# 01-LcdText1602.net
KiCad netlist of a schematic drawn in Altium Designer
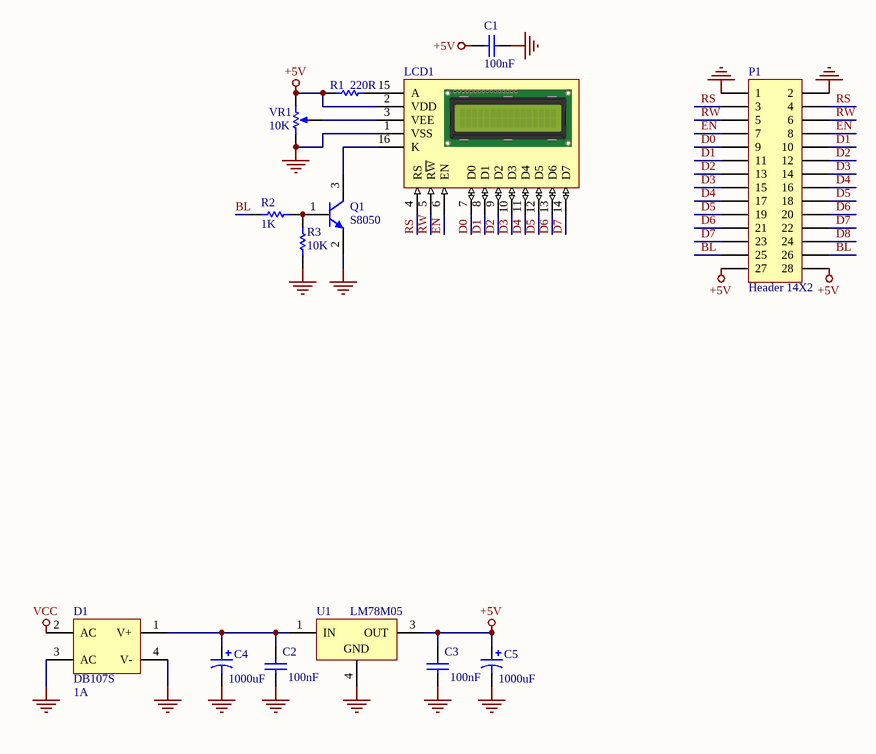
[diagram p0: 01-LcdText1602.SchDoc]

(export (version "E")
  (design (tool "Eeschema 10.0.6"))
  (components
    (comp (ref "C1")
      (value "100nF")
      (footprint "RAD-0.3")
      (description "Capacitor")
      (fields (field (name "Comment") "104") (field (name "PUBLISHER") "Altium Limited"))
      (libsource (lib "Miscellaneous Devices") (part "Cap"))
    )
    (comp (ref "C2")
      (value "100nF")
      (footprint "RAD-0.3")
      (description "Capacitor")
      (fields (field (name "Comment") "104") (field (name "PUBLISHER") "Altium Limited"))
      (libsource (lib "Miscellaneous Devices") (part "Cap"))
    )
    (comp (ref "C3")
      (value "100nF")
      (footprint "RAD-0.3")
      (description "Capacitor")
      (fields (field (name "Comment") "104") (field (name "PUBLISHER") "Altium Limited"))
      (libsource (lib "Miscellaneous Devices") (part "Cap"))
    )
    (comp (ref "C4")
      (value "1000uF")
      (footprint "RB7.6-15")
      (description "Polarized Capacitor (Radial)")
      (fields (field (name "Comment") "1000uF/16V") (field (name "PUBLISHER") "Altium Limited"))
      (libsource (lib "Miscellaneous Devices") (part "Cap Pol1"))
    )
    (comp (ref "C5")
      (value "1000uF")
      (footprint "RB7.6-15")
      (description "Polarized Capacitor (Radial)")
      (fields (field (name "Comment") "1000uF/16V") (field (name "PUBLISHER") "Altium Limited"))
      (libsource (lib "Miscellaneous Devices") (part "Cap Pol1"))
    )
    (comp (ref "D1")
      (value "DB107S")
      (footprint "D-46_6A")
      (description "Diode Bridge")
      (fields (field (name "ALTIUM_VALUE") "1A"))
      (libsource (lib "Miscellaneous Devices") (part "Bridge2"))
    )
    (comp (ref "LCD1")
      (value "16 x 2")
      (footprint "LCD16x2")
      (description "Liquid Crystal Display")
      (libsource (lib "Dlib") (part "LCD16X2"))
    )
    (comp (ref "P1")
      (value "Header 14X2")
      (footprint "HDR2X14")
      (description "Header, 14-Pin, Dual row")
      (fields (field (name "PUBLISHER") "Altium Limited"))
      (libsource (lib "Miscellaneous Connectors") (part "Header 14X2"))
    )
    (comp (ref "Q1")
      (value "S8050")
      (footprint "TO-226-AA")
      (description "NPN Bipolar Transistor")
      (libsource (lib "Miscellaneous Devices") (part "NPN"))
    )
    (comp (ref "R1")
      (value "220R")
      (footprint "AXIAL-0.3")
      (description "Resistor")
      (fields (field (name "PUBLISHER") "Altium Limited"))
      (libsource (lib "Miscellaneous Devices") (part "Res1"))
    )
    (comp (ref "R2")
      (value "1K")
      (footprint "AXIAL-0.3")
      (description "Resistor")
      (fields (field (name "PUBLISHER") "Altium Limited"))
      (libsource (lib "Miscellaneous Devices") (part "Res1"))
    )
    (comp (ref "R3")
      (value "10K")
      (footprint "AXIAL-0.3")
      (description "Resistor")
      (fields (field (name "PUBLISHER") "Altium Limited"))
      (libsource (lib "Miscellaneous Devices") (part "Res1"))
    )
    (comp (ref "U1")
      (value "LM78M05")
      (footprint "NDP0003B_M")
      (description "3-Terminal Positive Voltage Regulators, 3-pin TO-252")
      (fields (field (name "MANUFACTURER") "Texas Instruments") (field (name "Comment") "LM78M05CDTX"))
      (libsource (lib "Altium Content Vault") (part "CMP-0062-00204-3"))
    )
    (comp (ref "VR1")
      (value "10K")
      (footprint "VR5")
      (description "Potentiometer")
      (fields (field (name "PUBLISHER") "Altium Limited"))
      (libsource (lib "Miscellaneous Devices") (part "RPot"))
    )
  )
  (nets
    (net (code "1") (name "+5V") (class "Default")
      (node (ref "C1") (pin "1") (pinfunction "1_1") (pintype "passive"))
      (node (ref "C3") (pin "1") (pinfunction "1_1") (pintype "passive"))
      (node (ref "C5") (pin "1") (pinfunction "1_1") (pintype "passive"))
      (node (ref "LCD1") (pin "2") (pinfunction "VDD_2") (pintype "power_in"))
      (node (ref "P1") (pin "27") (pinfunction "27_27") (pintype "passive"))
      (node (ref "P1") (pin "28") (pinfunction "28_28") (pintype "passive"))
      (node (ref "R1") (pin "1") (pinfunction "1_1") (pintype "passive"))
      (node (ref "U1") (pin "3") (pinfunction "OUT_3") (pintype "power_in"))
      (node (ref "VR1") (pin "3") (pinfunction "BOT_3") (pintype "passive"))
    )
    (net (code "2") (name "/BL") (class "Default")
      (node (ref "P1") (pin "25") (pinfunction "25_25") (pintype "passive"))
      (node (ref "P1") (pin "26") (pinfunction "26_26") (pintype "passive"))
      (node (ref "R2") (pin "2") (pinfunction "2_2") (pintype "passive"))
    )
    (net (code "3") (name "/D0") (class "Default")
      (node (ref "LCD1") (pin "7") (pinfunction "D0_7") (pintype "bidirectional"))
      (node (ref "P1") (pin "9") (pinfunction "9_9") (pintype "passive"))
    )
    (net (code "4") (name "/D1") (class "Default")
      (node (ref "LCD1") (pin "8") (pinfunction "D1_8") (pintype "bidirectional"))
      (node (ref "P1") (pin "10") (pinfunction "10_10") (pintype "passive"))
      (node (ref "P1") (pin "11") (pinfunction "11_11") (pintype "passive"))
    )
    (net (code "5") (name "/D2") (class "Default")
      (node (ref "LCD1") (pin "9") (pinfunction "D2_9") (pintype "bidirectional"))
      (node (ref "P1") (pin "12") (pinfunction "12_12") (pintype "passive"))
      (node (ref "P1") (pin "13") (pinfunction "13_13") (pintype "passive"))
    )
    (net (code "6") (name "/D3") (class "Default")
      (node (ref "LCD1") (pin "10") (pinfunction "D3_10") (pintype "bidirectional"))
      (node (ref "P1") (pin "14") (pinfunction "14_14") (pintype "passive"))
      (node (ref "P1") (pin "15") (pinfunction "15_15") (pintype "passive"))
    )
    (net (code "7") (name "/D4") (class "Default")
      (node (ref "LCD1") (pin "11") (pinfunction "D4_11") (pintype "bidirectional"))
      (node (ref "P1") (pin "16") (pinfunction "16_16") (pintype "passive"))
      (node (ref "P1") (pin "17") (pinfunction "17_17") (pintype "passive"))
    )
    (net (code "8") (name "/D5") (class "Default")
      (node (ref "LCD1") (pin "12") (pinfunction "D5_12") (pintype "bidirectional"))
      (node (ref "P1") (pin "18") (pinfunction "18_18") (pintype "passive"))
      (node (ref "P1") (pin "19") (pinfunction "19_19") (pintype "passive"))
    )
    (net (code "9") (name "/D6") (class "Default")
      (node (ref "LCD1") (pin "13") (pinfunction "D6_13") (pintype "bidirectional"))
      (node (ref "P1") (pin "20") (pinfunction "20_20") (pintype "passive"))
      (node (ref "P1") (pin "21") (pinfunction "21_21") (pintype "passive"))
    )
    (net (code "10") (name "/D7") (class "Default")
      (node (ref "LCD1") (pin "14") (pinfunction "D7_14") (pintype "bidirectional"))
      (node (ref "P1") (pin "22") (pinfunction "22_22") (pintype "passive"))
      (node (ref "P1") (pin "23") (pinfunction "23_23") (pintype "passive"))
    )
    (net (code "11") (name "/D8") (class "Default")
      (node (ref "P1") (pin "24") (pinfunction "24_24") (pintype "passive"))
    )
    (net (code "12") (name "/EN") (class "Default")
      (node (ref "LCD1") (pin "6") (pinfunction "EN_6") (pintype "input"))
      (node (ref "P1") (pin "7") (pinfunction "7_7") (pintype "passive"))
      (node (ref "P1") (pin "8") (pinfunction "8_8") (pintype "passive"))
    )
    (net (code "13") (name "/RS") (class "Default")
      (node (ref "LCD1") (pin "4") (pinfunction "RS_4") (pintype "input"))
      (node (ref "P1") (pin "3") (pinfunction "3_3") (pintype "passive"))
      (node (ref "P1") (pin "4") (pinfunction "4_4") (pintype "passive"))
    )
    (net (code "14") (name "/RW") (class "Default")
      (node (ref "LCD1") (pin "5") (pinfunction "R~{W}_5") (pintype "input"))
      (node (ref "P1") (pin "5") (pinfunction "5_5") (pintype "passive"))
      (node (ref "P1") (pin "6") (pinfunction "6_6") (pintype "passive"))
    )
    (net (code "15") (name "GND") (class "Default")
      (node (ref "C1") (pin "2") (pinfunction "2_2") (pintype "passive"))
      (node (ref "C2") (pin "2") (pinfunction "2_2") (pintype "passive"))
      (node (ref "C3") (pin "2") (pinfunction "2_2") (pintype "passive"))
      (node (ref "C4") (pin "2") (pinfunction "2_2") (pintype "passive"))
      (node (ref "C5") (pin "2") (pinfunction "2_2") (pintype "passive"))
      (node (ref "D1") (pin "3") (pinfunction "AC_3") (pintype "passive"))
      (node (ref "D1") (pin "4") (pinfunction "V-_4") (pintype "passive"))
      (node (ref "LCD1") (pin "1") (pinfunction "VSS_1") (pintype "power_in"))
      (node (ref "P1") (pin "1") (pinfunction "1_1") (pintype "passive"))
      (node (ref "P1") (pin "2") (pinfunction "2_2") (pintype "passive"))
      (node (ref "Q1") (pin "2") (pinfunction "E_2") (pintype "passive"))
      (node (ref "R3") (pin "1") (pinfunction "1_1") (pintype "passive"))
      (node (ref "U1") (pin "4") (pinfunction "GND_4") (pintype "power_in"))
      (node (ref "VR1") (pin "1") (pinfunction "TOP_1") (pintype "passive"))
    )
    (net (code "16") (name "Net-(D1-V+)") (class "Default")
      (node (ref "C2") (pin "1") (pinfunction "1_1") (pintype "passive"))
      (node (ref "C4") (pin "1") (pinfunction "1_1") (pintype "passive"))
      (node (ref "D1") (pin "1") (pinfunction "V+_1") (pintype "passive"))
      (node (ref "U1") (pin "1") (pinfunction "IN_1") (pintype "power_in"))
    )
    (net (code "17") (name "Net-(LCD1-A)") (class "Default")
      (node (ref "LCD1") (pin "15") (pinfunction "A_15") (pintype "power_in"))
      (node (ref "R1") (pin "2") (pinfunction "2_2") (pintype "passive"))
    )
    (net (code "18") (name "Net-(LCD1-K)") (class "Default")
      (node (ref "LCD1") (pin "16") (pinfunction "K_16") (pintype "power_in"))
      (node (ref "Q1") (pin "3") (pinfunction "C_3") (pintype "passive"))
    )
    (net (code "19") (name "Net-(LCD1-VEE)") (class "Default")
      (node (ref "LCD1") (pin "3") (pinfunction "VEE_3") (pintype "power_in"))
      (node (ref "VR1") (pin "2") (pinfunction "TAP_2") (pintype "passive"))
    )
    (net (code "20") (name "Net-(Q1-B)") (class "Default")
      (node (ref "Q1") (pin "1") (pinfunction "B_1") (pintype "passive"))
      (node (ref "R2") (pin "1") (pinfunction "1_1") (pintype "passive"))
      (node (ref "R3") (pin "2") (pinfunction "2_2") (pintype "passive"))
    )
    (net (code "21") (name "VCC") (class "Default")
      (node (ref "D1") (pin "2") (pinfunction "AC_2") (pintype "passive"))
    )
  )
)
